# R3_CH340_Adapter.net
KiCad netlist of a schematic drawn in EAGLE
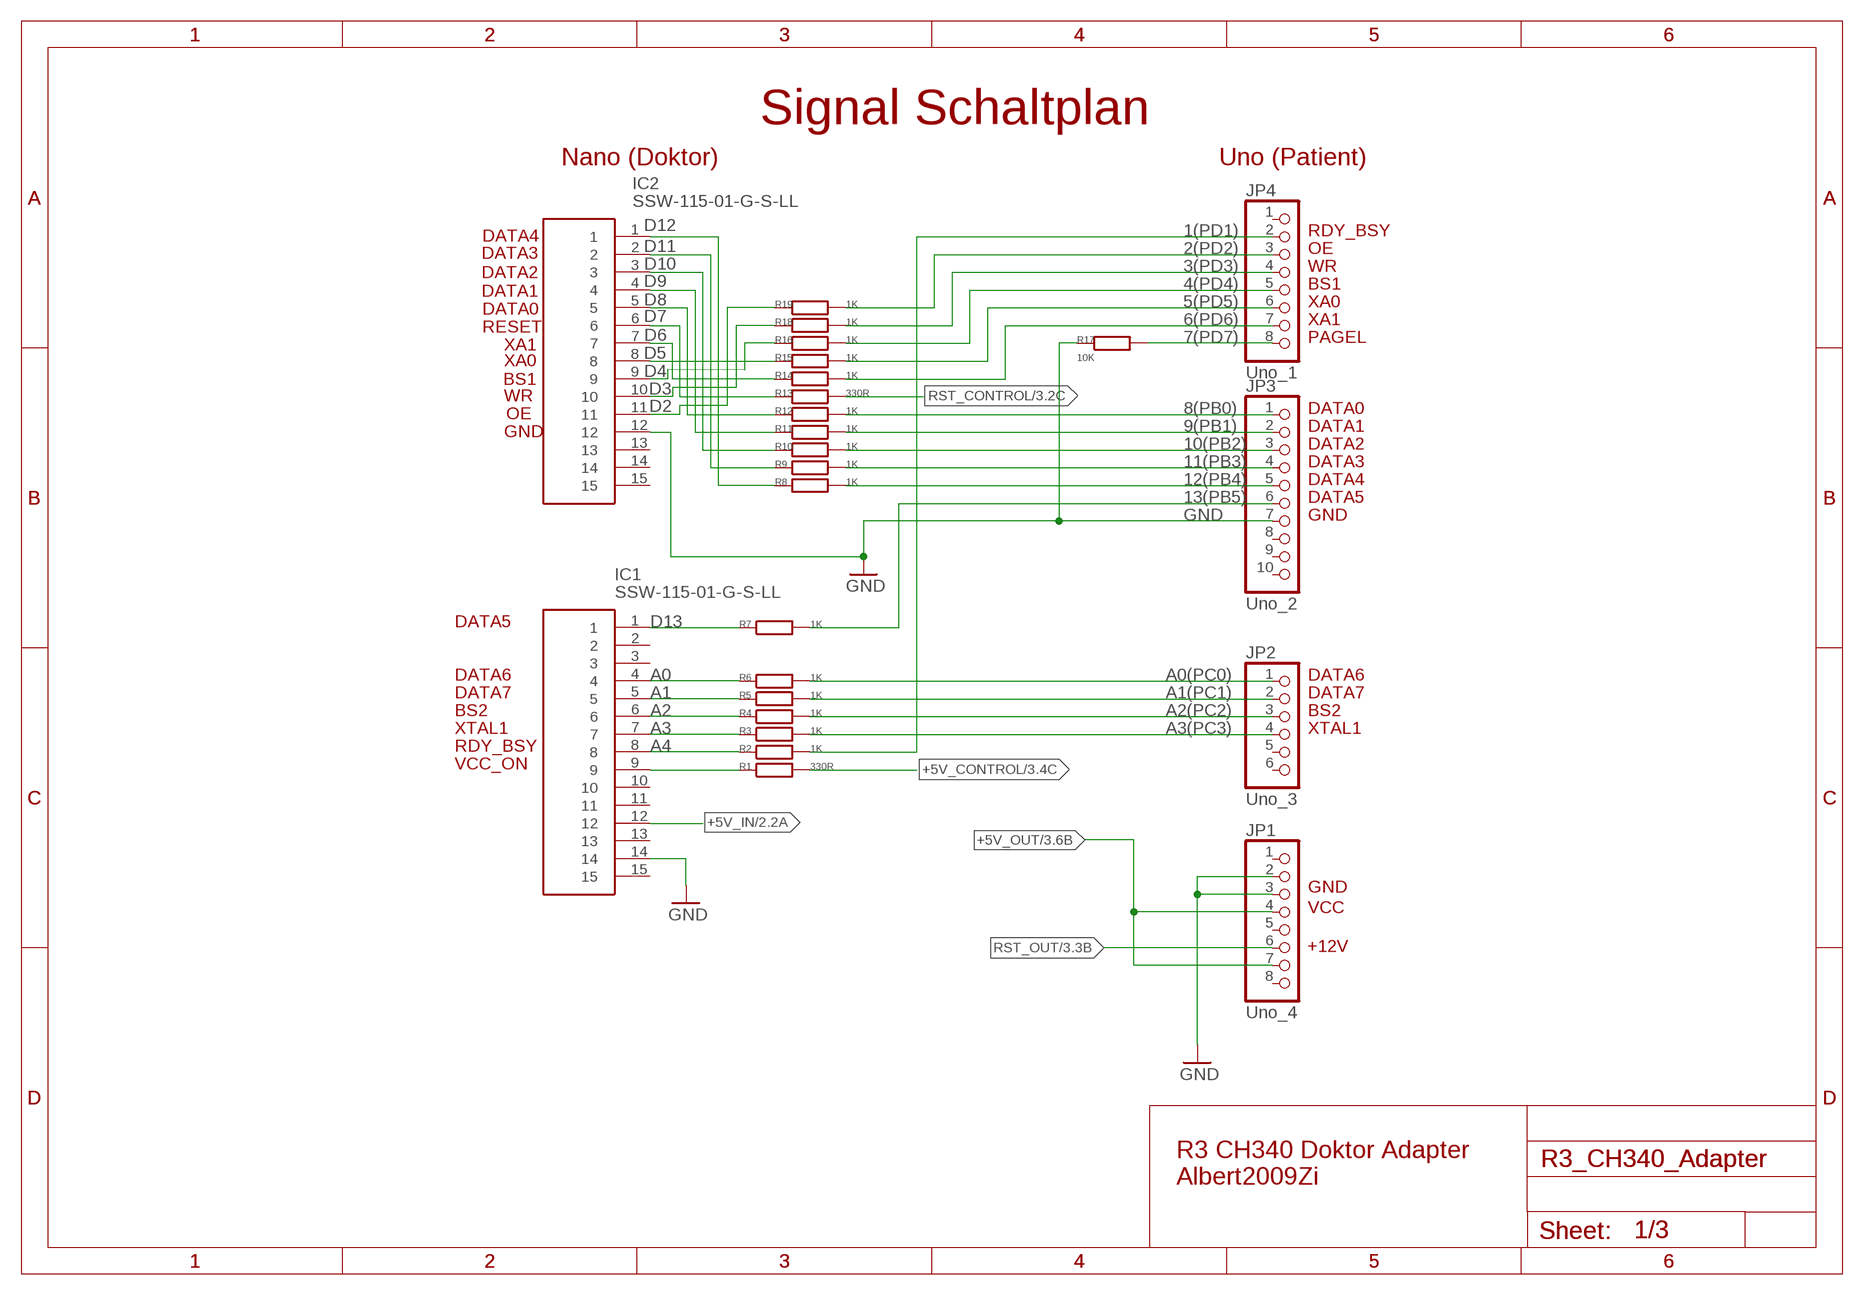
[diagram p0: schematic, sheet 1]
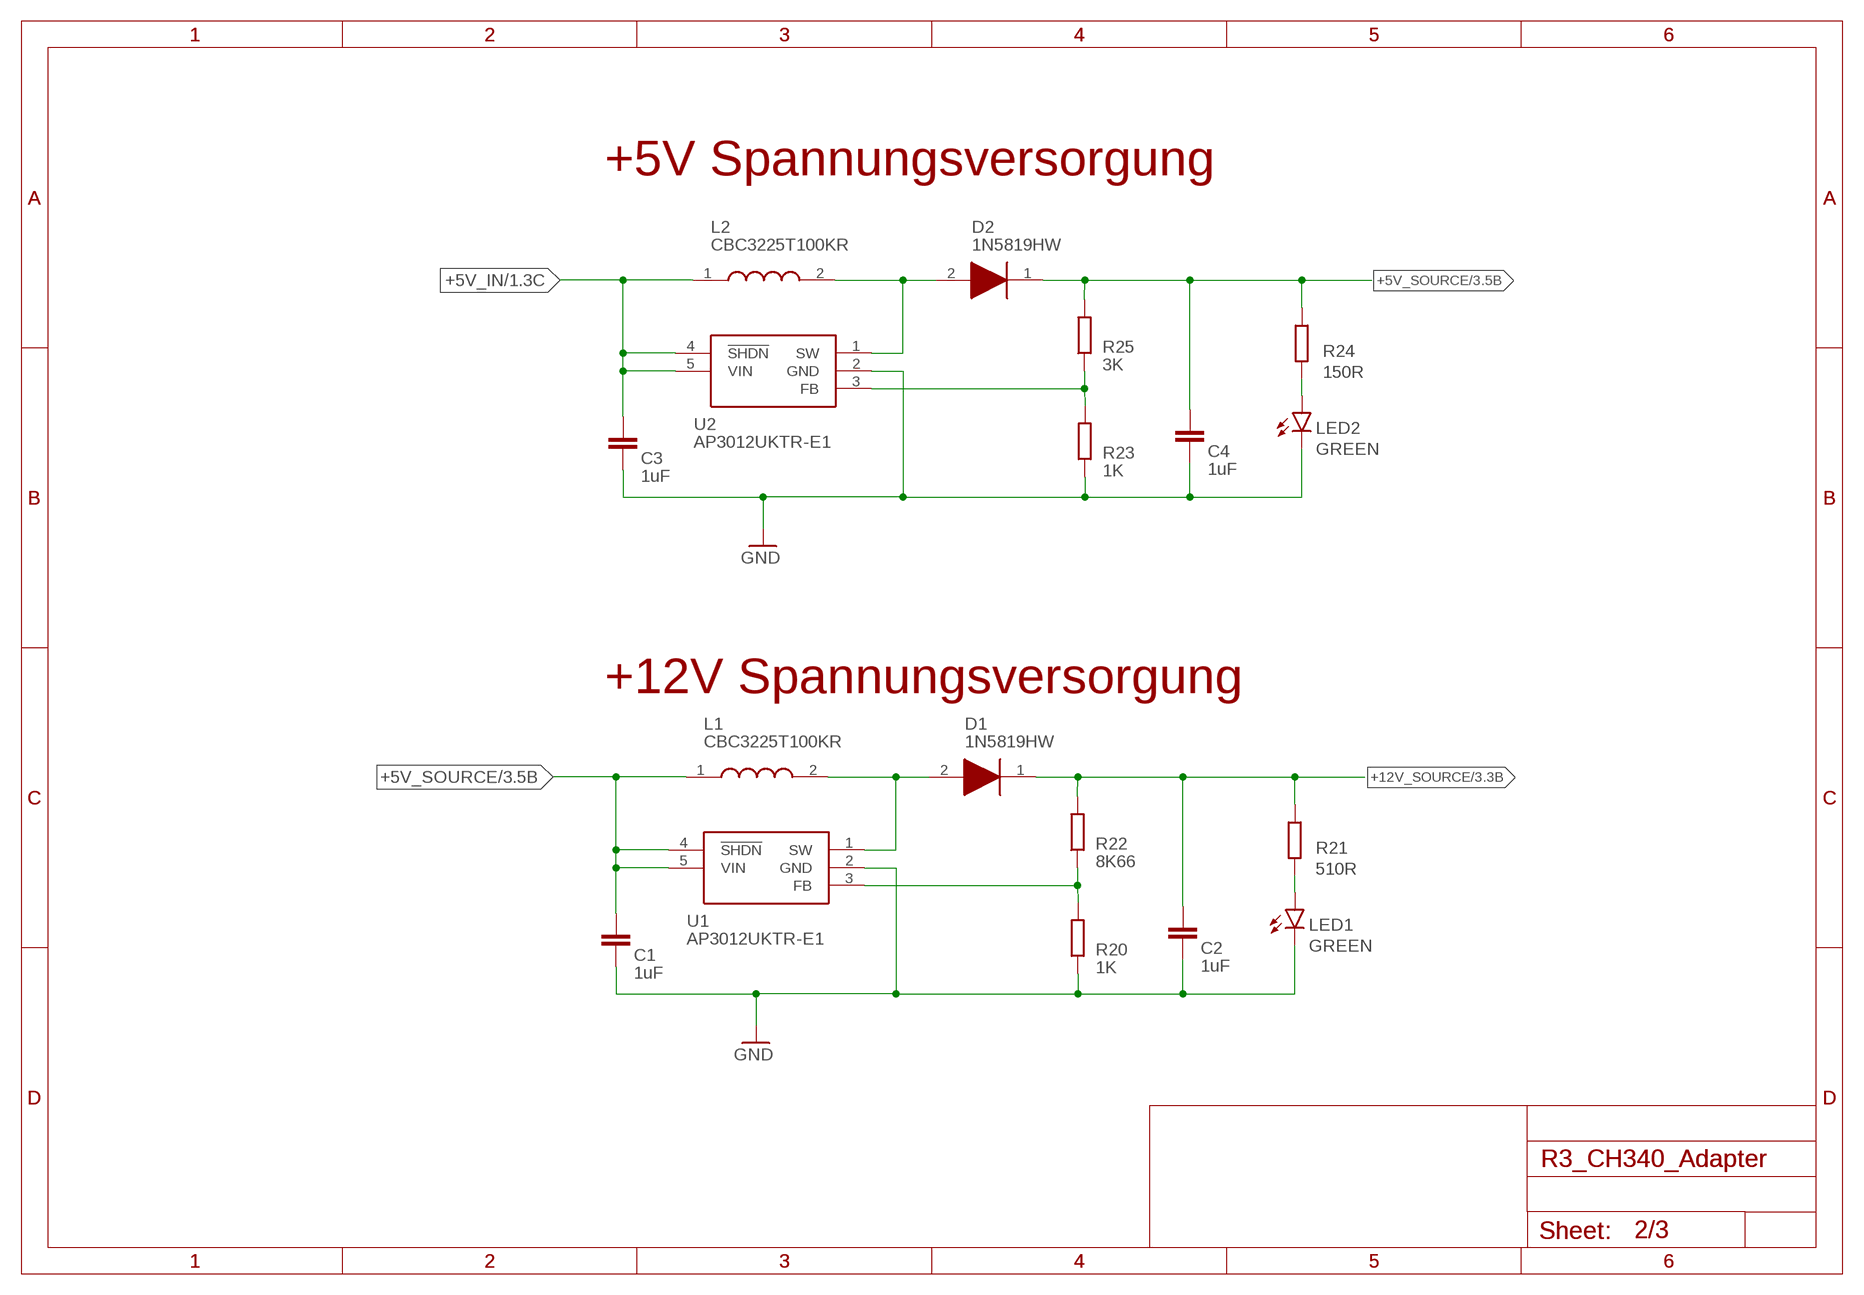
[diagram p1: schematic, sheet 2]
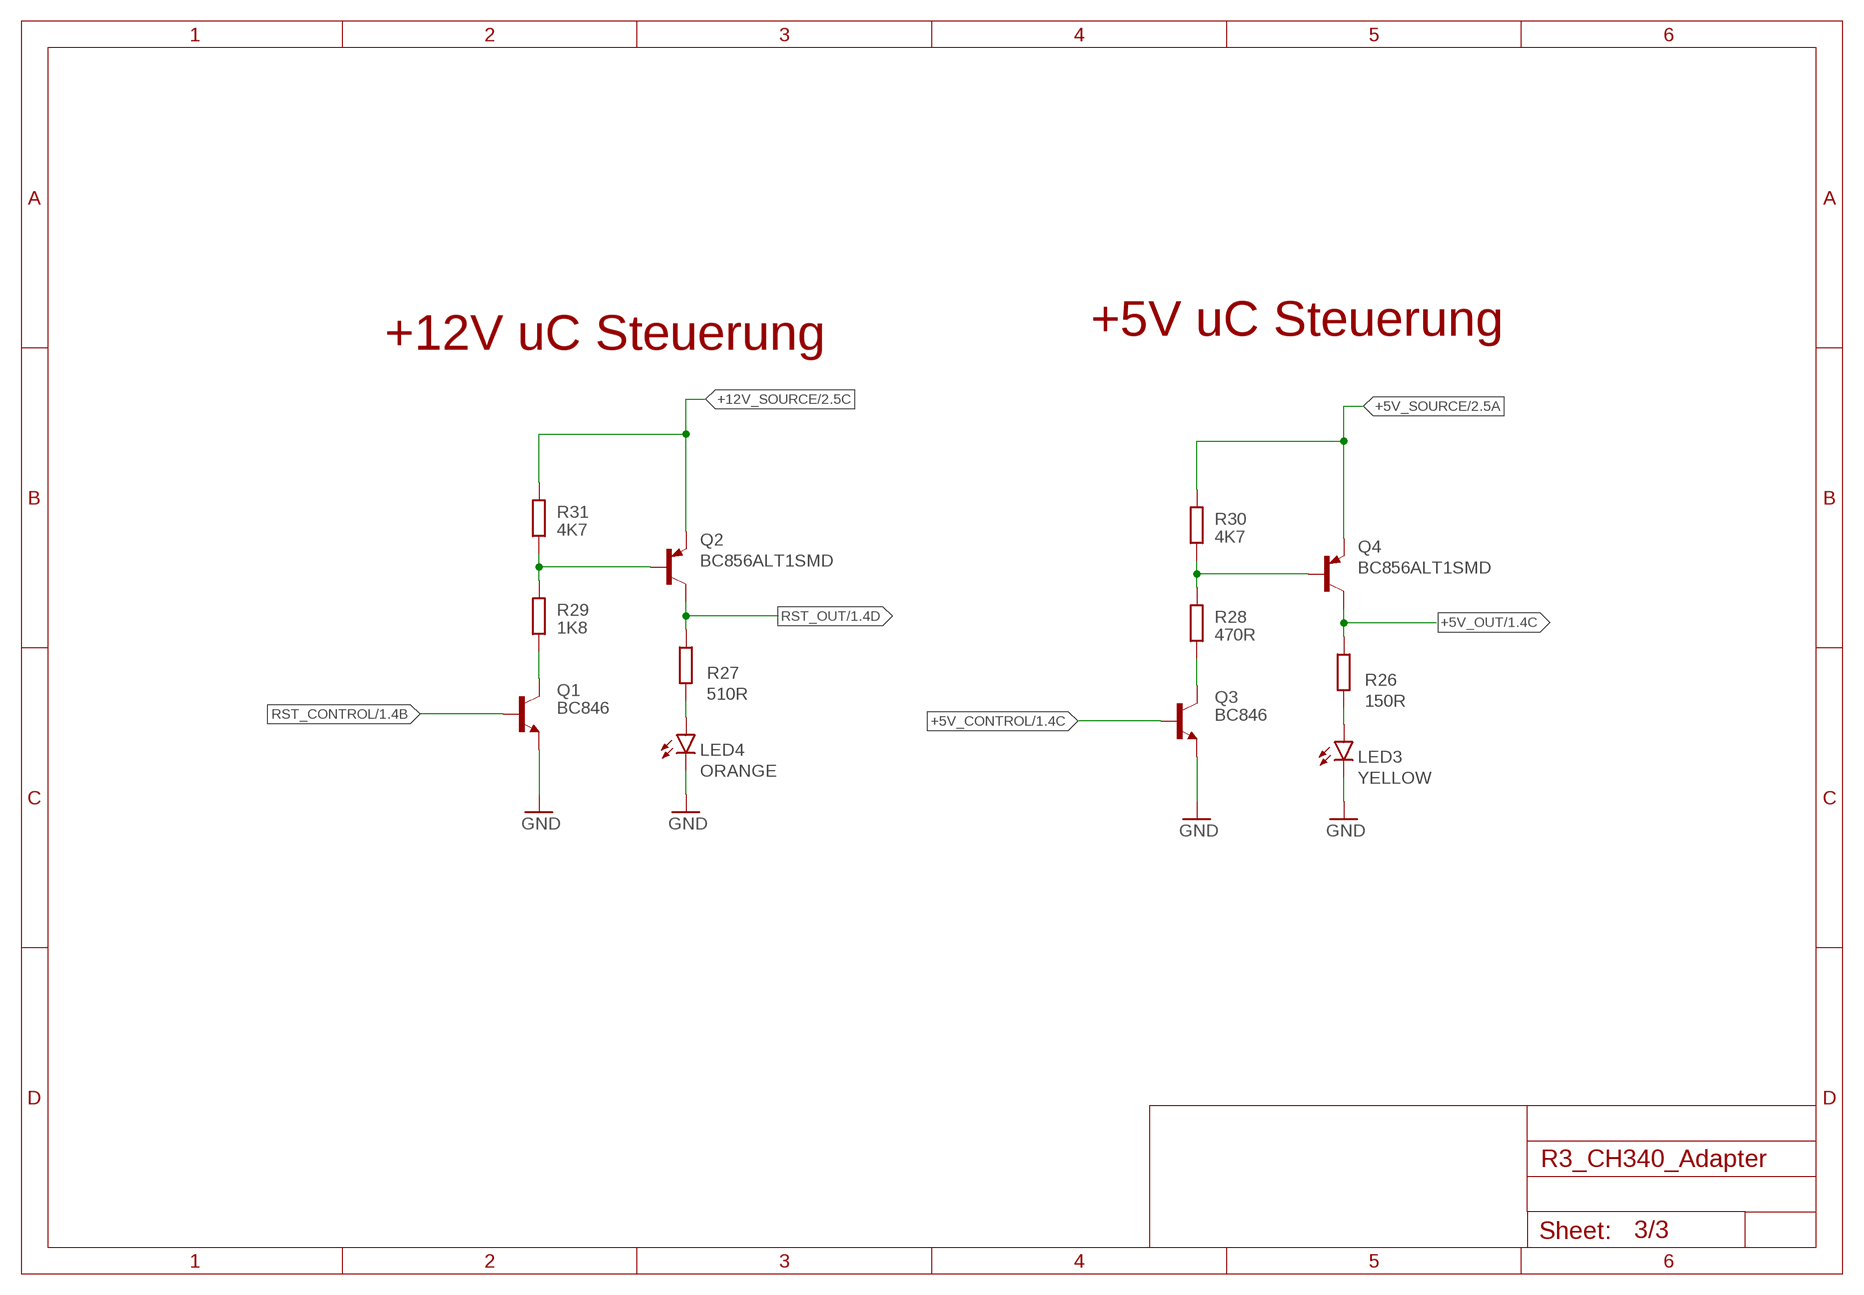
[diagram p2: schematic, sheet 3]

(export (version "E")
  (design (tool "Eeschema 10.0.6"))
  (components
    (comp (ref "IC1")
      (value "SSW-115-01-G-S-LL")
      (footprint "eagle-import:RHDR15W79P0X254_1X15_3861X241X")
      (fields (field (name "MOUSER_PART_NUMBER") "200-SSW11501GSLL"))
      (libsource (lib "eagle-import") (part "SSW-115-01-G-S-LL"))
    )
    (comp (ref "IC2")
      (value "SSW-115-01-G-S-LL")
      (footprint "eagle-import:RHDR15W79P0X254_1X15_3861X241X")
      (fields (field (name "MOUSER_PART_NUMBER") "200-SSW11501GSLL"))
      (libsource (lib "eagle-import") (part "SSW-115-01-G-S-LL"))
    )
    (comp (ref "JP1")
      (value "Uno_4")
      (footprint "eagle-import:1X08")
      (libsource (lib "eagle-import") (part "PINHD-1X8"))
    )
    (comp (ref "JP2")
      (value "Uno_3")
      (footprint "eagle-import:1X06")
      (libsource (lib "eagle-import") (part "PINHD-1X6"))
    )
    (comp (ref "JP3")
      (value "Uno_2")
      (footprint "eagle-import:1X10")
      (libsource (lib "eagle-import") (part "PINHD-1X10"))
    )
    (comp (ref "JP4")
      (value "Uno_1")
      (footprint "eagle-import:1X08")
      (libsource (lib "eagle-import") (part "PINHD-1X8"))
    )
    (comp (ref "R1")
      (value "330R")
      (footprint "eagle-import:R0805")
      (libsource (lib "eagle-import") (part "R-EU_R0805"))
    )
    (comp (ref "R2")
      (value "1K")
      (footprint "eagle-import:R0805")
      (libsource (lib "eagle-import") (part "R-EU_R0805"))
    )
    (comp (ref "R3")
      (value "1K")
      (footprint "eagle-import:R0805")
      (libsource (lib "eagle-import") (part "R-EU_R0805"))
    )
    (comp (ref "R4")
      (value "1K")
      (footprint "eagle-import:R0805")
      (libsource (lib "eagle-import") (part "R-EU_R0805"))
    )
    (comp (ref "R5")
      (value "1K")
      (footprint "eagle-import:R0805")
      (libsource (lib "eagle-import") (part "R-EU_R0805"))
    )
    (comp (ref "R6")
      (value "1K")
      (footprint "eagle-import:R0805")
      (libsource (lib "eagle-import") (part "R-EU_R0805"))
    )
    (comp (ref "R7")
      (value "1K")
      (footprint "eagle-import:R0805")
      (libsource (lib "eagle-import") (part "R-EU_R0805"))
    )
    (comp (ref "R8")
      (value "1K")
      (footprint "eagle-import:R0805")
      (libsource (lib "eagle-import") (part "R-EU_R0805"))
    )
    (comp (ref "R9")
      (value "1K")
      (footprint "eagle-import:R0805")
      (libsource (lib "eagle-import") (part "R-EU_R0805"))
    )
    (comp (ref "R10")
      (value "1K")
      (footprint "eagle-import:R0805")
      (libsource (lib "eagle-import") (part "R-EU_R0805"))
    )
    (comp (ref "R11")
      (value "1K")
      (footprint "eagle-import:R0805")
      (libsource (lib "eagle-import") (part "R-EU_R0805"))
    )
    (comp (ref "R12")
      (value "1K")
      (footprint "eagle-import:R0805")
      (libsource (lib "eagle-import") (part "R-EU_R0805"))
    )
    (comp (ref "R13")
      (value "330R")
      (footprint "eagle-import:R0805")
      (libsource (lib "eagle-import") (part "R-EU_R0805"))
    )
    (comp (ref "R14")
      (value "1K")
      (footprint "eagle-import:R0805")
      (libsource (lib "eagle-import") (part "R-EU_R0805"))
    )
    (comp (ref "R15")
      (value "1K")
      (footprint "eagle-import:R0805")
      (libsource (lib "eagle-import") (part "R-EU_R0805"))
    )
    (comp (ref "R16")
      (value "1K")
      (footprint "eagle-import:R0805")
      (libsource (lib "eagle-import") (part "R-EU_R0805"))
    )
    (comp (ref "R17")
      (value "10K")
      (footprint "eagle-import:R0805")
      (libsource (lib "eagle-import") (part "R-EU_R0805"))
    )
    (comp (ref "R18")
      (value "1K")
      (footprint "eagle-import:R0805")
      (libsource (lib "eagle-import") (part "R-EU_R0805"))
    )
    (comp (ref "R19")
      (value "1K")
      (footprint "eagle-import:R0805")
      (libsource (lib "eagle-import") (part "R-EU_R0805"))
    )
    (comp (ref "C1")
      (value "1uF")
      (footprint "eagle-import:C0805")
      (libsource (lib "eagle-import") (part "C-EUC0805"))
    )
    (comp (ref "C2")
      (value "1uF")
      (footprint "eagle-import:C0805")
      (libsource (lib "eagle-import") (part "C-EUC0805"))
    )
    (comp (ref "C3")
      (value "1uF")
      (footprint "eagle-import:C0805")
      (libsource (lib "eagle-import") (part "C-EUC0805"))
    )
    (comp (ref "C4")
      (value "1uF")
      (footprint "eagle-import:C0805")
      (libsource (lib "eagle-import") (part "C-EUC0805"))
    )
    (comp (ref "D1")
      (value "1N5819HW")
      (footprint "eagle-import:SOD3716X145N")
      (libsource (lib "eagle-import") (part "1N5819HW"))
    )
    (comp (ref "D2")
      (value "1N5819HW")
      (footprint "eagle-import:SOD3716X145N")
      (libsource (lib "eagle-import") (part "1N5819HW"))
    )
    (comp (ref "L1")
      (value "CBC3225T100KR")
      (footprint "eagle-import:INDC3225X270N")
      (fields (field (name "MOUSER_PART_NUMBER") "963-CBC3225T100KR"))
      (libsource (lib "eagle-import") (part "CBC3225T100KR"))
    )
    (comp (ref "L2")
      (value "CBC3225T100KR")
      (footprint "eagle-import:INDC3225X270N")
      (fields (field (name "MOUSER_PART_NUMBER") "963-CBC3225T100KR"))
      (libsource (lib "eagle-import") (part "CBC3225T100KR"))
    )
    (comp (ref "LED1")
      (value "GREEN")
      (footprint "eagle-import:CHIP-LED0805")
      (libsource (lib "eagle-import") (part "LEDCHIP-LED0805"))
    )
    (comp (ref "LED2")
      (value "GREEN")
      (footprint "eagle-import:CHIP-LED0805")
      (libsource (lib "eagle-import") (part "LEDCHIP-LED0805"))
    )
    (comp (ref "R20")
      (value "1K")
      (footprint "eagle-import:R0805")
      (libsource (lib "eagle-import") (part "R-EU_R0805"))
    )
    (comp (ref "R21")
      (value "510R")
      (footprint "eagle-import:R0805")
      (libsource (lib "eagle-import") (part "R-EU_R0805"))
    )
    (comp (ref "R22")
      (value "8K66")
      (footprint "eagle-import:R0805")
      (libsource (lib "eagle-import") (part "R-EU_R0805"))
    )
    (comp (ref "R23")
      (value "1K")
      (footprint "eagle-import:R0805")
      (libsource (lib "eagle-import") (part "R-EU_R0805"))
    )
    (comp (ref "R24")
      (value "150R")
      (footprint "eagle-import:R0805")
      (libsource (lib "eagle-import") (part "R-EU_R0805"))
    )
    (comp (ref "R25")
      (value "3K")
      (footprint "eagle-import:R0805")
      (libsource (lib "eagle-import") (part "R-EU_R0805"))
    )
    (comp (ref "U1")
      (value "AP3012UKTR-E1")
      (footprint "eagle-import:SOT95P280X145-5N")
      (fields (field (name "MOUSER_PART_NUMBER") "621-AP3012UKTR-E1"))
      (libsource (lib "eagle-import") (part "AP3012UKTR-E1"))
    )
    (comp (ref "U2")
      (value "AP3012UKTR-E1")
      (footprint "eagle-import:SOT95P280X145-5N")
      (fields (field (name "MOUSER_PART_NUMBER") "621-AP3012UKTR-E1"))
      (libsource (lib "eagle-import") (part "AP3012UKTR-E1"))
    )
    (comp (ref "LED3")
      (value "YELLOW")
      (footprint "eagle-import:CHIP-LED0805")
      (libsource (lib "eagle-import") (part "LEDCHIP-LED0805"))
    )
    (comp (ref "LED4")
      (value "ORANGE")
      (footprint "eagle-import:CHIP-LED0805")
      (libsource (lib "eagle-import") (part "LEDCHIP-LED0805"))
    )
    (comp (ref "Q1")
      (value "BC846")
      (footprint "eagle-import:SOT23")
      (libsource (lib "eagle-import") (part "BC846"))
    )
    (comp (ref "Q2")
      (value "BC856ALT1SMD")
      (footprint "eagle-import:SOT23-BEC")
      (libsource (lib "eagle-import") (part "BC856SMDALT1"))
    )
    (comp (ref "Q3")
      (value "BC846")
      (footprint "eagle-import:SOT23")
      (libsource (lib "eagle-import") (part "BC846"))
    )
    (comp (ref "Q4")
      (value "BC856ALT1SMD")
      (footprint "eagle-import:SOT23-BEC")
      (libsource (lib "eagle-import") (part "BC856SMDALT1"))
    )
    (comp (ref "R26")
      (value "150R")
      (footprint "eagle-import:R0805")
      (libsource (lib "eagle-import") (part "R-EU_R0805"))
    )
    (comp (ref "R27")
      (value "510R")
      (footprint "eagle-import:R0805")
      (libsource (lib "eagle-import") (part "R-EU_R0805"))
    )
    (comp (ref "R28")
      (value "470R")
      (footprint "eagle-import:R0805")
      (libsource (lib "eagle-import") (part "R-EU_R0805"))
    )
    (comp (ref "R29")
      (value "1K8")
      (footprint "eagle-import:R0805")
      (libsource (lib "eagle-import") (part "R-EU_R0805"))
    )
    (comp (ref "R30")
      (value "4K7")
      (footprint "eagle-import:R0805")
      (libsource (lib "eagle-import") (part "R-EU_R0805"))
    )
    (comp (ref "R31")
      (value "4K7")
      (footprint "eagle-import:R0805")
      (libsource (lib "eagle-import") (part "R-EU_R0805"))
    )
  )
  (nets
    (net (code "1") (name "+5V_CONTROL") (class "Default")
      (node (ref "Q3") (pin "1") (pinfunction "B_1") (pintype "passive"))
      (node (ref "R1") (pin "2") (pinfunction "2_2") (pintype "passive"))
    )
    (net (code "2") (name "+5V_IN") (class "Default")
      (node (ref "C3") (pin "1") (pinfunction "1_1") (pintype "passive"))
      (node (ref "IC1") (pin "12") (pinfunction "12_12") (pintype "bidirectional"))
      (node (ref "L2") (pin "1") (pinfunction "1_1") (pintype "bidirectional"))
      (node (ref "U2") (pin "4") (pinfunction "~{SHDN}_4") (pintype "bidirectional"))
      (node (ref "U2") (pin "5") (pinfunction "VIN_5") (pintype "bidirectional"))
    )
    (net (code "3") (name "+5V_OUT") (class "Default")
      (node (ref "JP1") (pin "4") (pinfunction "4_4") (pintype "passive"))
      (node (ref "JP1") (pin "7") (pinfunction "7_7") (pintype "passive"))
      (node (ref "Q4") (pin "C") (pinfunction "C_C") (pintype "passive"))
      (node (ref "R26") (pin "1") (pinfunction "1_1") (pintype "passive"))
    )
    (net (code "4") (name "+5V_SOURCE") (class "Default")
      (node (ref "C1") (pin "1") (pinfunction "1_1") (pintype "passive"))
      (node (ref "C4") (pin "1") (pinfunction "1_1") (pintype "passive"))
      (node (ref "D2") (pin "1") (pinfunction "K_1") (pintype "bidirectional"))
      (node (ref "L1") (pin "1") (pinfunction "1_1") (pintype "bidirectional"))
      (node (ref "Q4") (pin "E") (pinfunction "E_E") (pintype "passive"))
      (node (ref "R24") (pin "1") (pinfunction "1_1") (pintype "passive"))
      (node (ref "R25") (pin "2") (pinfunction "2_2") (pintype "passive"))
      (node (ref "R30") (pin "2") (pinfunction "2_2") (pintype "passive"))
      (node (ref "U1") (pin "4") (pinfunction "~{SHDN}_4") (pintype "bidirectional"))
      (node (ref "U1") (pin "5") (pinfunction "VIN_5") (pintype "bidirectional"))
    )
    (net (code "5") (name "+12V_SOURCE") (class "Default")
      (node (ref "C2") (pin "1") (pinfunction "1_1") (pintype "passive"))
      (node (ref "D1") (pin "1") (pinfunction "K_1") (pintype "bidirectional"))
      (node (ref "Q2") (pin "E") (pinfunction "E_E") (pintype "passive"))
      (node (ref "R21") (pin "1") (pinfunction "1_1") (pintype "passive"))
      (node (ref "R22") (pin "2") (pinfunction "2_2") (pintype "passive"))
      (node (ref "R31") (pin "2") (pinfunction "2_2") (pintype "passive"))
    )
    (net (code "6") (name "1(PD1)") (class "Default")
      (node (ref "JP4") (pin "2") (pinfunction "2_2") (pintype "passive"))
      (node (ref "R2") (pin "2") (pinfunction "2_2") (pintype "passive"))
    )
    (net (code "7") (name "2(PD2)") (class "Default")
      (node (ref "JP4") (pin "3") (pinfunction "3_3") (pintype "passive"))
      (node (ref "R19") (pin "2") (pinfunction "2_2") (pintype "passive"))
    )
    (net (code "8") (name "3(PD3)") (class "Default")
      (node (ref "JP4") (pin "4") (pinfunction "4_4") (pintype "passive"))
      (node (ref "R18") (pin "2") (pinfunction "2_2") (pintype "passive"))
    )
    (net (code "9") (name "4(PD4)") (class "Default")
      (node (ref "JP4") (pin "5") (pinfunction "5_5") (pintype "passive"))
      (node (ref "R16") (pin "2") (pinfunction "2_2") (pintype "passive"))
    )
    (net (code "10") (name "5(PD5)") (class "Default")
      (node (ref "JP4") (pin "6") (pinfunction "6_6") (pintype "passive"))
      (node (ref "R15") (pin "2") (pinfunction "2_2") (pintype "passive"))
    )
    (net (code "11") (name "6(PD6)") (class "Default")
      (node (ref "JP4") (pin "7") (pinfunction "7_7") (pintype "passive"))
      (node (ref "R14") (pin "2") (pinfunction "2_2") (pintype "passive"))
    )
    (net (code "12") (name "7(PD7)") (class "Default")
      (node (ref "JP4") (pin "8") (pinfunction "8_8") (pintype "passive"))
      (node (ref "R17") (pin "2") (pinfunction "2_2") (pintype "passive"))
    )
    (net (code "13") (name "8(PB0)") (class "Default")
      (node (ref "JP3") (pin "1") (pinfunction "1_1") (pintype "passive"))
      (node (ref "R12") (pin "2") (pinfunction "2_2") (pintype "passive"))
    )
    (net (code "14") (name "9(PB1)") (class "Default")
      (node (ref "JP3") (pin "2") (pinfunction "2_2") (pintype "passive"))
      (node (ref "R11") (pin "2") (pinfunction "2_2") (pintype "passive"))
    )
    (net (code "15") (name "10(PB2)") (class "Default")
      (node (ref "JP3") (pin "3") (pinfunction "3_3") (pintype "passive"))
      (node (ref "R10") (pin "2") (pinfunction "2_2") (pintype "passive"))
    )
    (net (code "16") (name "11(PB3)") (class "Default")
      (node (ref "JP3") (pin "4") (pinfunction "4_4") (pintype "passive"))
      (node (ref "R9") (pin "2") (pinfunction "2_2") (pintype "passive"))
    )
    (net (code "17") (name "12(PB4)") (class "Default")
      (node (ref "JP3") (pin "5") (pinfunction "5_5") (pintype "passive"))
      (node (ref "R8") (pin "2") (pinfunction "2_2") (pintype "passive"))
    )
    (net (code "18") (name "13(PB5)") (class "Default")
      (node (ref "JP3") (pin "6") (pinfunction "6_6") (pintype "passive"))
      (node (ref "R7") (pin "2") (pinfunction "2_2") (pintype "passive"))
    )
    (net (code "19") (name "A0") (class "Default")
      (node (ref "IC1") (pin "4") (pinfunction "4_4") (pintype "bidirectional"))
      (node (ref "R6") (pin "1") (pinfunction "1_1") (pintype "passive"))
    )
    (net (code "20") (name "A0(PC0)") (class "Default")
      (node (ref "JP2") (pin "1") (pinfunction "1_1") (pintype "passive"))
      (node (ref "R6") (pin "2") (pinfunction "2_2") (pintype "passive"))
    )
    (net (code "21") (name "A1") (class "Default")
      (node (ref "IC1") (pin "5") (pinfunction "5_5") (pintype "bidirectional"))
      (node (ref "R5") (pin "1") (pinfunction "1_1") (pintype "passive"))
    )
    (net (code "22") (name "A1(PC1)") (class "Default")
      (node (ref "JP2") (pin "2") (pinfunction "2_2") (pintype "passive"))
      (node (ref "R5") (pin "2") (pinfunction "2_2") (pintype "passive"))
    )
    (net (code "23") (name "A2") (class "Default")
      (node (ref "IC1") (pin "6") (pinfunction "6_6") (pintype "bidirectional"))
      (node (ref "R4") (pin "1") (pinfunction "1_1") (pintype "passive"))
    )
    (net (code "24") (name "A2(PC2)") (class "Default")
      (node (ref "JP2") (pin "3") (pinfunction "3_3") (pintype "passive"))
      (node (ref "R4") (pin "2") (pinfunction "2_2") (pintype "passive"))
    )
    (net (code "25") (name "A3") (class "Default")
      (node (ref "IC1") (pin "7") (pinfunction "7_7") (pintype "bidirectional"))
      (node (ref "R3") (pin "1") (pinfunction "1_1") (pintype "passive"))
    )
    (net (code "26") (name "A3(PC3)") (class "Default")
      (node (ref "JP2") (pin "4") (pinfunction "4_4") (pintype "passive"))
      (node (ref "R3") (pin "2") (pinfunction "2_2") (pintype "passive"))
    )
    (net (code "27") (name "A4") (class "Default")
      (node (ref "IC1") (pin "8") (pinfunction "8_8") (pintype "bidirectional"))
      (node (ref "R2") (pin "1") (pinfunction "1_1") (pintype "passive"))
    )
    (net (code "28") (name "D2") (class "Default")
      (node (ref "IC2") (pin "11") (pinfunction "11_11") (pintype "bidirectional"))
      (node (ref "R19") (pin "1") (pinfunction "1_1") (pintype "passive"))
    )
    (net (code "29") (name "D3") (class "Default")
      (node (ref "IC2") (pin "10") (pinfunction "10_10") (pintype "bidirectional"))
      (node (ref "R18") (pin "1") (pinfunction "1_1") (pintype "passive"))
    )
    (net (code "30") (name "D4") (class "Default")
      (node (ref "IC2") (pin "9") (pinfunction "9_9") (pintype "bidirectional"))
      (node (ref "R16") (pin "1") (pinfunction "1_1") (pintype "passive"))
    )
    (net (code "31") (name "D5") (class "Default")
      (node (ref "IC2") (pin "8") (pinfunction "8_8") (pintype "bidirectional"))
      (node (ref "R15") (pin "1") (pinfunction "1_1") (pintype "passive"))
    )
    (net (code "32") (name "D6") (class "Default")
      (node (ref "IC2") (pin "7") (pinfunction "7_7") (pintype "bidirectional"))
      (node (ref "R14") (pin "1") (pinfunction "1_1") (pintype "passive"))
    )
    (net (code "33") (name "D7") (class "Default")
      (node (ref "IC2") (pin "6") (pinfunction "6_6") (pintype "bidirectional"))
      (node (ref "R13") (pin "1") (pinfunction "1_1") (pintype "passive"))
    )
    (net (code "34") (name "D8") (class "Default")
      (node (ref "IC2") (pin "5") (pinfunction "5_5") (pintype "bidirectional"))
      (node (ref "R12") (pin "1") (pinfunction "1_1") (pintype "passive"))
    )
    (net (code "35") (name "D9") (class "Default")
      (node (ref "IC2") (pin "4") (pinfunction "4_4") (pintype "bidirectional"))
      (node (ref "R11") (pin "1") (pinfunction "1_1") (pintype "passive"))
    )
    (net (code "36") (name "D10") (class "Default")
      (node (ref "IC2") (pin "3") (pinfunction "3_3") (pintype "bidirectional"))
      (node (ref "R10") (pin "1") (pinfunction "1_1") (pintype "passive"))
    )
    (net (code "37") (name "D11") (class "Default")
      (node (ref "IC2") (pin "2") (pinfunction "2_2") (pintype "bidirectional"))
      (node (ref "R9") (pin "1") (pinfunction "1_1") (pintype "passive"))
    )
    (net (code "38") (name "D12") (class "Default")
      (node (ref "IC2") (pin "1") (pinfunction "1_1") (pintype "bidirectional"))
      (node (ref "R8") (pin "1") (pinfunction "1_1") (pintype "passive"))
    )
    (net (code "39") (name "D13") (class "Default")
      (node (ref "IC1") (pin "1") (pinfunction "1_1") (pintype "bidirectional"))
      (node (ref "R7") (pin "1") (pinfunction "1_1") (pintype "passive"))
    )
    (net (code "40") (name "GND") (class "Default")
      (node (ref "C1") (pin "2") (pinfunction "2_2") (pintype "passive"))
      (node (ref "C2") (pin "2") (pinfunction "2_2") (pintype "passive"))
      (node (ref "C3") (pin "2") (pinfunction "2_2") (pintype "passive"))
      (node (ref "C4") (pin "2") (pinfunction "2_2") (pintype "passive"))
      (node (ref "IC1") (pin "14") (pinfunction "14_14") (pintype "bidirectional"))
      (node (ref "IC2") (pin "12") (pinfunction "12_12") (pintype "bidirectional"))
      (node (ref "JP1") (pin "2") (pinfunction "2_2") (pintype "passive"))
      (node (ref "JP1") (pin "3") (pinfunction "3_3") (pintype "passive"))
      (node (ref "JP3") (pin "7") (pinfunction "7_7") (pintype "passive"))
      (node (ref "LED1") (pin "C") (pinfunction "C_C") (pintype "passive"))
      (node (ref "LED2") (pin "C") (pinfunction "C_C") (pintype "passive"))
      (node (ref "LED3") (pin "C") (pinfunction "C_C") (pintype "passive"))
      (node (ref "LED4") (pin "C") (pinfunction "C_C") (pintype "passive"))
      (node (ref "Q1") (pin "2") (pinfunction "E_2") (pintype "passive"))
      (node (ref "Q3") (pin "2") (pinfunction "E_2") (pintype "passive"))
      (node (ref "R17") (pin "1") (pinfunction "1_1") (pintype "passive"))
      (node (ref "R20") (pin "1") (pinfunction "1_1") (pintype "passive"))
      (node (ref "R23") (pin "1") (pinfunction "1_1") (pintype "passive"))
      (node (ref "U1") (pin "2") (pinfunction "GND_2") (pintype "bidirectional"))
      (node (ref "U2") (pin "2") (pinfunction "GND_2") (pintype "bidirectional"))
    )
    (net (code "41") (name "Net-(D1-A)") (class "Default")
      (node (ref "D1") (pin "2") (pinfunction "A_2") (pintype "bidirectional"))
      (node (ref "L1") (pin "2") (pinfunction "2_2") (pintype "bidirectional"))
      (node (ref "U1") (pin "1") (pinfunction "SW_1") (pintype "bidirectional"))
    )
    (net (code "42") (name "Net-(D2-A)") (class "Default")
      (node (ref "D2") (pin "2") (pinfunction "A_2") (pintype "bidirectional"))
      (node (ref "L2") (pin "2") (pinfunction "2_2") (pintype "bidirectional"))
      (node (ref "U2") (pin "1") (pinfunction "SW_1") (pintype "bidirectional"))
    )
    (net (code "43") (name "Net-(IC1-Pad9)") (class "Default")
      (node (ref "IC1") (pin "9") (pinfunction "9_9") (pintype "bidirectional"))
      (node (ref "R1") (pin "1") (pinfunction "1_1") (pintype "passive"))
    )
    (net (code "44") (name "Net-(LED1-PadA)") (class "Default")
      (node (ref "LED1") (pin "A") (pinfunction "A_A") (pintype "passive"))
      (node (ref "R21") (pin "2") (pinfunction "2_2") (pintype "passive"))
    )
    (net (code "45") (name "Net-(LED2-PadA)") (class "Default")
      (node (ref "LED2") (pin "A") (pinfunction "A_A") (pintype "passive"))
      (node (ref "R24") (pin "2") (pinfunction "2_2") (pintype "passive"))
    )
    (net (code "46") (name "Net-(LED3-PadA)") (class "Default")
      (node (ref "LED3") (pin "A") (pinfunction "A_A") (pintype "passive"))
      (node (ref "R26") (pin "2") (pinfunction "2_2") (pintype "passive"))
    )
    (net (code "47") (name "Net-(LED4-PadA)") (class "Default")
      (node (ref "LED4") (pin "A") (pinfunction "A_A") (pintype "passive"))
      (node (ref "R27") (pin "2") (pinfunction "2_2") (pintype "passive"))
    )
    (net (code "48") (name "Net-(Q1-C)") (class "Default")
      (node (ref "Q1") (pin "3") (pinfunction "C_3") (pintype "passive"))
      (node (ref "R29") (pin "1") (pinfunction "1_1") (pintype "passive"))
    )
    (net (code "49") (name "Net-(Q2-PadB)") (class "Default")
      (node (ref "Q2") (pin "B") (pinfunction "B_B") (pintype "passive"))
      (node (ref "R29") (pin "2") (pinfunction "2_2") (pintype "passive"))
      (node (ref "R31") (pin "1") (pinfunction "1_1") (pintype "passive"))
    )
    (net (code "50") (name "Net-(Q3-C)") (class "Default")
      (node (ref "Q3") (pin "3") (pinfunction "C_3") (pintype "passive"))
      (node (ref "R28") (pin "1") (pinfunction "1_1") (pintype "passive"))
    )
    (net (code "51") (name "Net-(Q4-PadB)") (class "Default")
      (node (ref "Q4") (pin "B") (pinfunction "B_B") (pintype "passive"))
      (node (ref "R28") (pin "2") (pinfunction "2_2") (pintype "passive"))
      (node (ref "R30") (pin "1") (pinfunction "1_1") (pintype "passive"))
    )
    (net (code "52") (name "Net-(U1-FB)") (class "Default")
      (node (ref "R20") (pin "2") (pinfunction "2_2") (pintype "passive"))
      (node (ref "R22") (pin "1") (pinfunction "1_1") (pintype "passive"))
      (node (ref "U1") (pin "3") (pinfunction "FB_3") (pintype "bidirectional"))
    )
    (net (code "53") (name "Net-(U2-FB)") (class "Default")
      (node (ref "R23") (pin "2") (pinfunction "2_2") (pintype "passive"))
      (node (ref "R25") (pin "1") (pinfunction "1_1") (pintype "passive"))
      (node (ref "U2") (pin "3") (pinfunction "FB_3") (pintype "bidirectional"))
    )
    (net (code "54") (name "RST_CONTROL") (class "Default")
      (node (ref "Q1") (pin "1") (pinfunction "B_1") (pintype "passive"))
      (node (ref "R13") (pin "2") (pinfunction "2_2") (pintype "passive"))
    )
    (net (code "55") (name "RST_OUT") (class "Default")
      (node (ref "JP1") (pin "6") (pinfunction "6_6") (pintype "passive"))
      (node (ref "Q2") (pin "C") (pinfunction "C_C") (pintype "passive"))
      (node (ref "R27") (pin "1") (pinfunction "1_1") (pintype "passive"))
    )
    (net (code "56") (name "unconnected-(IC1-Pad2)") (class "Default")
      (node (ref "IC1") (pin "2") (pinfunction "2_2") (pintype "bidirectional"))
    )
    (net (code "57") (name "unconnected-(IC1-Pad3)") (class "Default")
      (node (ref "IC1") (pin "3") (pinfunction "3_3") (pintype "bidirectional"))
    )
    (net (code "58") (name "unconnected-(IC1-Pad10)") (class "Default")
      (node (ref "IC1") (pin "10") (pinfunction "10_10") (pintype "bidirectional"))
    )
    (net (code "59") (name "unconnected-(IC1-Pad11)") (class "Default")
      (node (ref "IC1") (pin "11") (pinfunction "11_11") (pintype "bidirectional"))
    )
    (net (code "60") (name "unconnected-(IC1-Pad13)") (class "Default")
      (node (ref "IC1") (pin "13") (pinfunction "13_13") (pintype "bidirectional"))
    )
    (net (code "61") (name "unconnected-(IC1-Pad15)") (class "Default")
      (node (ref "IC1") (pin "15") (pinfunction "15_15") (pintype "bidirectional"))
    )
    (net (code "62") (name "unconnected-(IC2-Pad13)") (class "Default")
      (node (ref "IC2") (pin "13") (pinfunction "13_13") (pintype "bidirectional"))
    )
    (net (code "63") (name "unconnected-(IC2-Pad14)") (class "Default")
      (node (ref "IC2") (pin "14") (pinfunction "14_14") (pintype "bidirectional"))
    )
    (net (code "64") (name "unconnected-(IC2-Pad15)") (class "Default")
      (node (ref "IC2") (pin "15") (pinfunction "15_15") (pintype "bidirectional"))
    )
    (net (code "65") (name "unconnected-(JP1-Pad1)") (class "Default")
      (node (ref "JP1") (pin "1") (pinfunction "1_1") (pintype "passive"))
    )
    (net (code "66") (name "unconnected-(JP1-Pad5)") (class "Default")
      (node (ref "JP1") (pin "5") (pinfunction "5_5") (pintype "passive"))
    )
    (net (code "67") (name "unconnected-(JP1-Pad8)") (class "Default")
      (node (ref "JP1") (pin "8") (pinfunction "8_8") (pintype "passive"))
    )
    (net (code "68") (name "unconnected-(JP2-Pad5)") (class "Default")
      (node (ref "JP2") (pin "5") (pinfunction "5_5") (pintype "passive"))
    )
    (net (code "69") (name "unconnected-(JP2-Pad6)") (class "Default")
      (node (ref "JP2") (pin "6") (pinfunction "6_6") (pintype "passive"))
    )
    (net (code "70") (name "unconnected-(JP3-Pad8)") (class "Default")
      (node (ref "JP3") (pin "8") (pinfunction "8_8") (pintype "passive"))
    )
    (net (code "71") (name "unconnected-(JP3-Pad9)") (class "Default")
      (node (ref "JP3") (pin "9") (pinfunction "9_9") (pintype "passive"))
    )
    (net (code "72") (name "unconnected-(JP3-Pad10)") (class "Default")
      (node (ref "JP3") (pin "10") (pinfunction "10_10") (pintype "passive"))
    )
    (net (code "73") (name "unconnected-(JP4-Pad1)") (class "Default")
      (node (ref "JP4") (pin "1") (pinfunction "1_1") (pintype "passive"))
    )
  )
)
